# SWD.net
KiCad netlist of a schematic drawn in Altium Designer
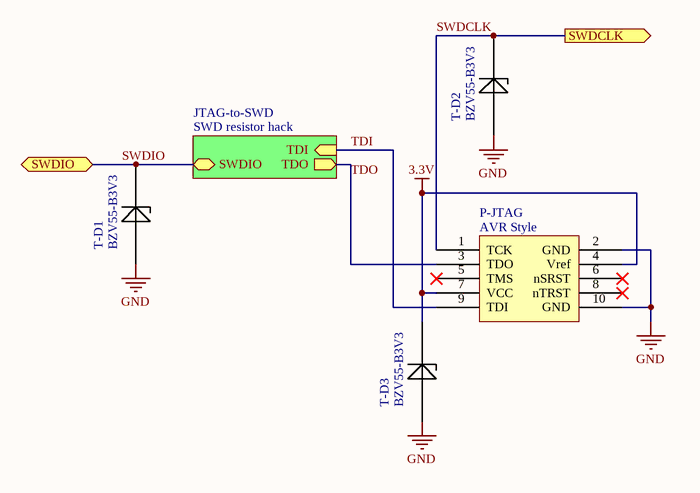
[diagram p0: SWD.SchDoc]

(export (version "E")
  (design (tool "Eeschema 10.0.6"))
  (components
    (comp (ref "P-JTAG")
      (value "AVR Style")
      (footprint "Header 2x5 IDC-10S")
      (libsource (lib "Headers") (part "Header JTAG AVR"))
    )
    (comp (ref "T-D1")
      (value "BZV55-B3V3")
      (footprint "Minimelf")
      (libsource (lib "Standard") (part "Zener Diode"))
    )
    (comp (ref "T-D2")
      (value "BZV55-B3V3")
      (footprint "Minimelf")
      (libsource (lib "Standard") (part "Zener Diode"))
    )
    (comp (ref "T-D3")
      (value "BZV55-B3V3")
      (footprint "Minimelf")
      (libsource (lib "Standard") (part "Zener Diode"))
    )
  )
  (nets
    (net (code "1") (name "/SWDCLK") (class "Default")
      (node (ref "P-JTAG") (pin "1") (pinfunction "TCK_1") (pintype "passive"))
      (node (ref "T-D2") (pin "1") (pinfunction "1_1") (pintype "passive"))
    )
    (net (code "2") (name "/SWDIO") (class "Default")
      (node (ref "T-D1") (pin "1") (pinfunction "1_1") (pintype "passive"))
    )
    (net (code "3") (name "/TDI") (class "Default")
      (node (ref "P-JTAG") (pin "9") (pinfunction "TDI_9") (pintype "passive"))
    )
    (net (code "4") (name "/TDO") (class "Default")
      (node (ref "P-JTAG") (pin "3") (pinfunction "TDO_3") (pintype "passive"))
    )
    (net (code "5") (name "3.3V") (class "Default")
      (node (ref "P-JTAG") (pin "4") (pinfunction "Vref_4") (pintype "passive"))
      (node (ref "P-JTAG") (pin "7") (pinfunction "VCC_7") (pintype "passive"))
      (node (ref "T-D3") (pin "1") (pinfunction "1_1") (pintype "passive"))
    )
    (net (code "6") (name "GND") (class "Default")
      (node (ref "P-JTAG") (pin "10") (pinfunction "GND_10") (pintype "passive"))
      (node (ref "P-JTAG") (pin "2") (pinfunction "GND_2") (pintype "passive"))
      (node (ref "T-D1") (pin "2") (pinfunction "2_2") (pintype "passive"))
      (node (ref "T-D2") (pin "2") (pinfunction "2_2") (pintype "passive"))
      (node (ref "T-D3") (pin "2") (pinfunction "2_2") (pintype "passive"))
    )
    (net (code "7") (name "unconnected-(P-JTAG-TMS-Pad5)") (class "Default")
      (node (ref "P-JTAG") (pin "5") (pinfunction "TMS_5") (pintype "passive+no_connect"))
    )
    (net (code "8") (name "unconnected-(P-JTAG-nSRST-Pad6)") (class "Default")
      (node (ref "P-JTAG") (pin "6") (pinfunction "nSRST_6") (pintype "passive+no_connect"))
    )
    (net (code "9") (name "unconnected-(P-JTAG-nTRST-Pad8)") (class "Default")
      (node (ref "P-JTAG") (pin "8") (pinfunction "nTRST_8") (pintype "passive+no_connect"))
    )
  )
)
